# attiny45-microcontrol-v4_2-small-bts409l.net
KiCad netlist of a schematic drawn in EAGLE
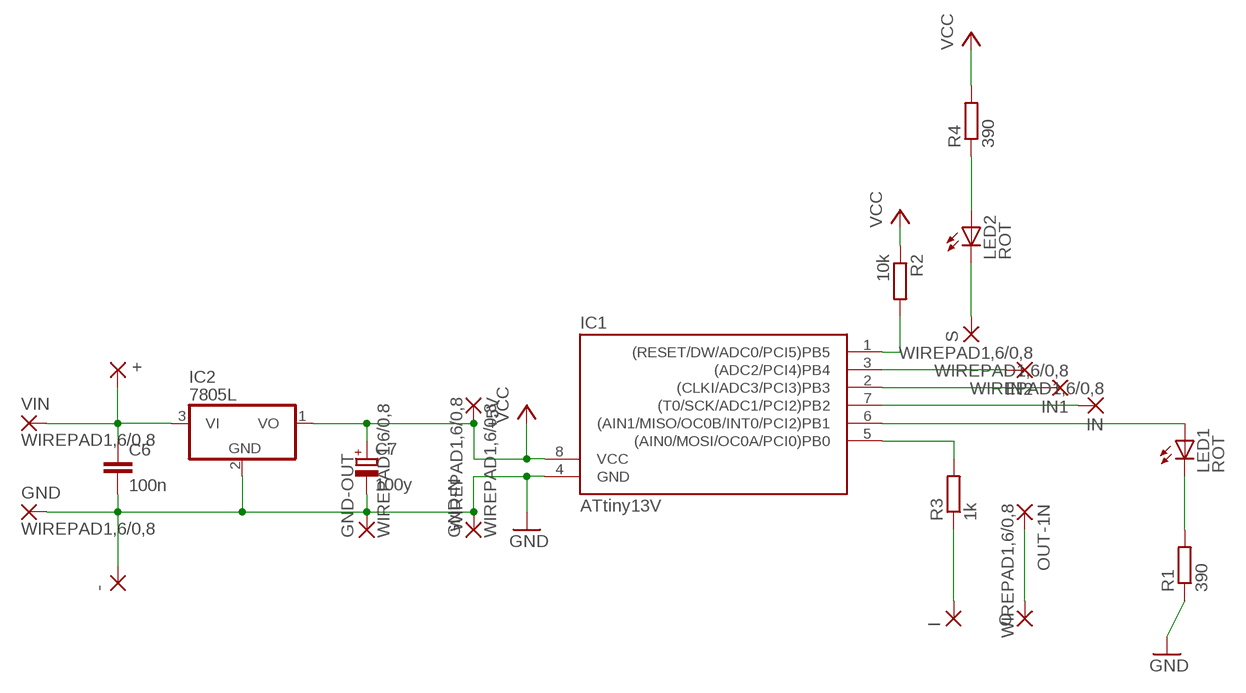
[diagram p0: schematic, sheet 1]

(export (version "E")
  (design (tool "Eeschema 10.0.6"))
  (components
    (comp (ref "+")
      (value "SMD2")
      (footprint "eagle-import:SMD1,27-2,54")
      (libsource (lib "eagle-import") (part "SMD2"))
    )
    (comp (ref "+5V")
      (value "WIREPAD1,6/0,8")
      (footprint "eagle-import:1,6_0,8")
      (libsource (lib "eagle-import") (part "WIREPAD1,6/0,8"))
    )
    (comp (ref "-")
      (value "SMD2")
      (footprint "eagle-import:SMD1,27-2,54")
      (libsource (lib "eagle-import") (part "SMD2"))
    )
    (comp (ref "C6")
      (value "100n")
      (footprint "eagle-import:C050-035X075")
      (libsource (lib "eagle-import") (part "C-EU050-035X075"))
    )
    (comp (ref "C7")
      (value "100y")
      (footprint "eagle-import:E2,5-5")
      (libsource (lib "eagle-import") (part "CPOL-EUE2.5-5"))
    )
    (comp (ref "GND")
      (value "WIREPAD1,6/0,8")
      (footprint "eagle-import:1,6_0,8")
      (libsource (lib "eagle-import") (part "WIREPAD1,6/0,8"))
    )
    (comp (ref "GND-N")
      (value "WIREPAD1,6/0,8")
      (footprint "eagle-import:1,6_0,8")
      (libsource (lib "eagle-import") (part "WIREPAD1,6/0,8"))
    )
    (comp (ref "GND-OUT")
      (value "WIREPAD1,6/0,8")
      (footprint "eagle-import:1,6_0,8")
      (libsource (lib "eagle-import") (part "WIREPAD1,6/0,8"))
    )
    (comp (ref "I")
      (value "SMD2")
      (footprint "eagle-import:SMD1,27-2,54")
      (libsource (lib "eagle-import") (part "SMD2"))
    )
    (comp (ref "IC1")
      (value "ATtiny13V")
      (footprint "eagle-import:DIL08")
      (libsource (lib "eagle-import") (part "ATTINY13P-20"))
    )
    (comp (ref "IC2")
      (value "7805L")
      (footprint "eagle-import:TO92")
      (libsource (lib "eagle-import") (part "78L05"))
    )
    (comp (ref "IN")
      (value "WIREPAD1,6/0,8")
      (footprint "eagle-import:1,6_0,8")
      (libsource (lib "eagle-import") (part "WIREPAD1,6/0,8"))
    )
    (comp (ref "IN1")
      (value "WIREPAD1,6/0,8")
      (footprint "eagle-import:1,6_0,8")
      (libsource (lib "eagle-import") (part "WIREPAD1,6/0,8"))
    )
    (comp (ref "IN2")
      (value "WIREPAD1,6/0,8")
      (footprint "eagle-import:1,6_0,8")
      (libsource (lib "eagle-import") (part "WIREPAD1,6/0,8"))
    )
    (comp (ref "LED1")
      (value "ROT")
      (footprint "eagle-import:LED3MM")
      (libsource (lib "eagle-import") (part "LED3MM"))
    )
    (comp (ref "LED2")
      (value "ROT")
      (footprint "eagle-import:LED3MM")
      (libsource (lib "eagle-import") (part "LED3MM"))
    )
    (comp (ref "O")
      (value "SMD2")
      (footprint "eagle-import:SMD1,27-2,54")
      (libsource (lib "eagle-import") (part "SMD2"))
    )
    (comp (ref "OUT-1N")
      (value "WIREPAD1,6/0,8")
      (footprint "eagle-import:1,6_0,8")
      (libsource (lib "eagle-import") (part "WIREPAD1,6/0,8"))
    )
    (comp (ref "R1")
      (value "390")
      (footprint "eagle-import:0204_5")
      (libsource (lib "eagle-import") (part "R-EU_0204/5"))
    )
    (comp (ref "R2")
      (value "10k")
      (footprint "eagle-import:R1206")
      (libsource (lib "eagle-import") (part "R-EU_R1206"))
    )
    (comp (ref "R3")
      (value "1k")
      (footprint "eagle-import:0207_7")
      (libsource (lib "eagle-import") (part "R-EU_0207/7"))
    )
    (comp (ref "R4")
      (value "390")
      (footprint "eagle-import:0204_5")
      (libsource (lib "eagle-import") (part "R-EU_0204/5"))
    )
    (comp (ref "S")
      (value "SMD2")
      (footprint "eagle-import:SMD1,27-2,54")
      (libsource (lib "eagle-import") (part "SMD2"))
    )
    (comp (ref "VIN")
      (value "WIREPAD1,6/0,8")
      (footprint "eagle-import:1,6_0,8")
      (libsource (lib "eagle-import") (part "WIREPAD1,6/0,8"))
    )
  )
  (nets
    (net (code "1") (name "GND") (class "Default")
      (node (ref "-") (pin "1") (pinfunction "P_1") (pintype "passive"))
      (node (ref "C6") (pin "2") (pinfunction "2_2") (pintype "passive"))
      (node (ref "C7") (pin "-") (pinfunction "-_-") (pintype "passive"))
      (node (ref "GND") (pin "1") (pinfunction "P_1") (pintype "passive"))
      (node (ref "GND-N") (pin "1") (pinfunction "P_1") (pintype "passive"))
      (node (ref "GND-OUT") (pin "1") (pinfunction "P_1") (pintype "passive"))
      (node (ref "IC1") (pin "4") (pinfunction "GND_4") (pintype "power_in"))
      (node (ref "IC2") (pin "2") (pinfunction "GND_2") (pintype "passive"))
      (node (ref "R1") (pin "1") (pinfunction "1_1") (pintype "passive"))
    )
    (net (code "2") (name "Net-(+-P)") (class "Default")
      (node (ref "+") (pin "1") (pinfunction "P_1") (pintype "passive"))
      (node (ref "C6") (pin "1") (pinfunction "1_1") (pintype "passive"))
      (node (ref "IC2") (pin "3") (pinfunction "VI_3") (pintype "input"))
      (node (ref "VIN") (pin "1") (pinfunction "P_1") (pintype "passive"))
    )
    (net (code "3") (name "Net-(I-P)") (class "Default")
      (node (ref "I") (pin "1") (pinfunction "P_1") (pintype "passive"))
      (node (ref "R3") (pin "1") (pinfunction "1_1") (pintype "passive"))
    )
    (net (code "4") (name "Net-(IC1-(ADC2{slash}PCI4)PB4)") (class "Default")
      (node (ref "IC1") (pin "3") (pinfunction "(ADC2/PCI4)PB4_3") (pintype "bidirectional"))
      (node (ref "IN2") (pin "1") (pinfunction "P_1") (pintype "passive"))
    )
    (net (code "5") (name "Net-(IC1-(AIN0{slash}MOSI{slash}OC0A{slash}PCI0)PB0)") (class "Default")
      (node (ref "IC1") (pin "5") (pinfunction "(AIN0/MOSI/OC0A/PCI0)PB0_5") (pintype "bidirectional"))
      (node (ref "R3") (pin "2") (pinfunction "2_2") (pintype "passive"))
    )
    (net (code "6") (name "Net-(IC1-(AIN1{slash}MISO{slash}OC0B{slash}INT0{slash}PCI2)PB1)") (class "Default")
      (node (ref "IC1") (pin "6") (pinfunction "(AIN1/MISO/OC0B/INT0/PCI2)PB1_6") (pintype "bidirectional"))
      (node (ref "LED1") (pin "A") (pinfunction "A_A") (pintype "passive"))
    )
    (net (code "7") (name "Net-(IC1-(CLKI{slash}ADC3{slash}PCI3)PB3)") (class "Default")
      (node (ref "IC1") (pin "2") (pinfunction "(CLKI/ADC3/PCI3)PB3_2") (pintype "bidirectional"))
      (node (ref "IN1") (pin "1") (pinfunction "P_1") (pintype "passive"))
    )
    (net (code "8") (name "Net-(IC1-(RESET{slash}DW{slash}ADC0{slash}PCI5)PB5)") (class "Default")
      (node (ref "IC1") (pin "1") (pinfunction "(RESET/DW/ADC0/PCI5)PB5_1") (pintype "bidirectional"))
      (node (ref "R2") (pin "2") (pinfunction "2_2") (pintype "passive"))
    )
    (net (code "9") (name "Net-(IC1-(T0{slash}SCK{slash}ADC1{slash}PCI2)PB2)") (class "Default")
      (node (ref "IC1") (pin "7") (pinfunction "(T0/SCK/ADC1/PCI2)PB2_7") (pintype "bidirectional"))
      (node (ref "IN") (pin "1") (pinfunction "P_1") (pintype "passive"))
    )
    (net (code "10") (name "Net-(LED1-C)") (class "Default")
      (node (ref "LED1") (pin "K") (pinfunction "C_K") (pintype "passive"))
      (node (ref "R1") (pin "2") (pinfunction "2_2") (pintype "passive"))
    )
    (net (code "11") (name "Net-(LED2-C)") (class "Default")
      (node (ref "LED2") (pin "K") (pinfunction "C_K") (pintype "passive"))
      (node (ref "S") (pin "1") (pinfunction "P_1") (pintype "passive"))
    )
    (net (code "12") (name "Net-(LED2-PadA)") (class "Default")
      (node (ref "LED2") (pin "A") (pinfunction "A_A") (pintype "passive"))
      (node (ref "R4") (pin "1") (pinfunction "1_1") (pintype "passive"))
    )
    (net (code "13") (name "Net-(O-P)") (class "Default")
      (node (ref "O") (pin "1") (pinfunction "P_1") (pintype "passive"))
      (node (ref "OUT-1N") (pin "1") (pinfunction "P_1") (pintype "passive"))
    )
    (net (code "14") (name "VCC") (class "Default")
      (node (ref "+5V") (pin "1") (pinfunction "P_1") (pintype "passive"))
      (node (ref "C7") (pin "+") (pinfunction "+_+") (pintype "passive"))
      (node (ref "IC1") (pin "8") (pinfunction "VCC_8") (pintype "power_in"))
      (node (ref "IC2") (pin "1") (pinfunction "VO_1") (pintype "passive"))
      (node (ref "R2") (pin "1") (pinfunction "1_1") (pintype "passive"))
      (node (ref "R4") (pin "2") (pinfunction "2_2") (pintype "passive"))
    )
  )
)
